# 12V_-_5V_Buck_1A_-_LM3485_v2.net
KiCad netlist of a schematic drawn in EAGLE
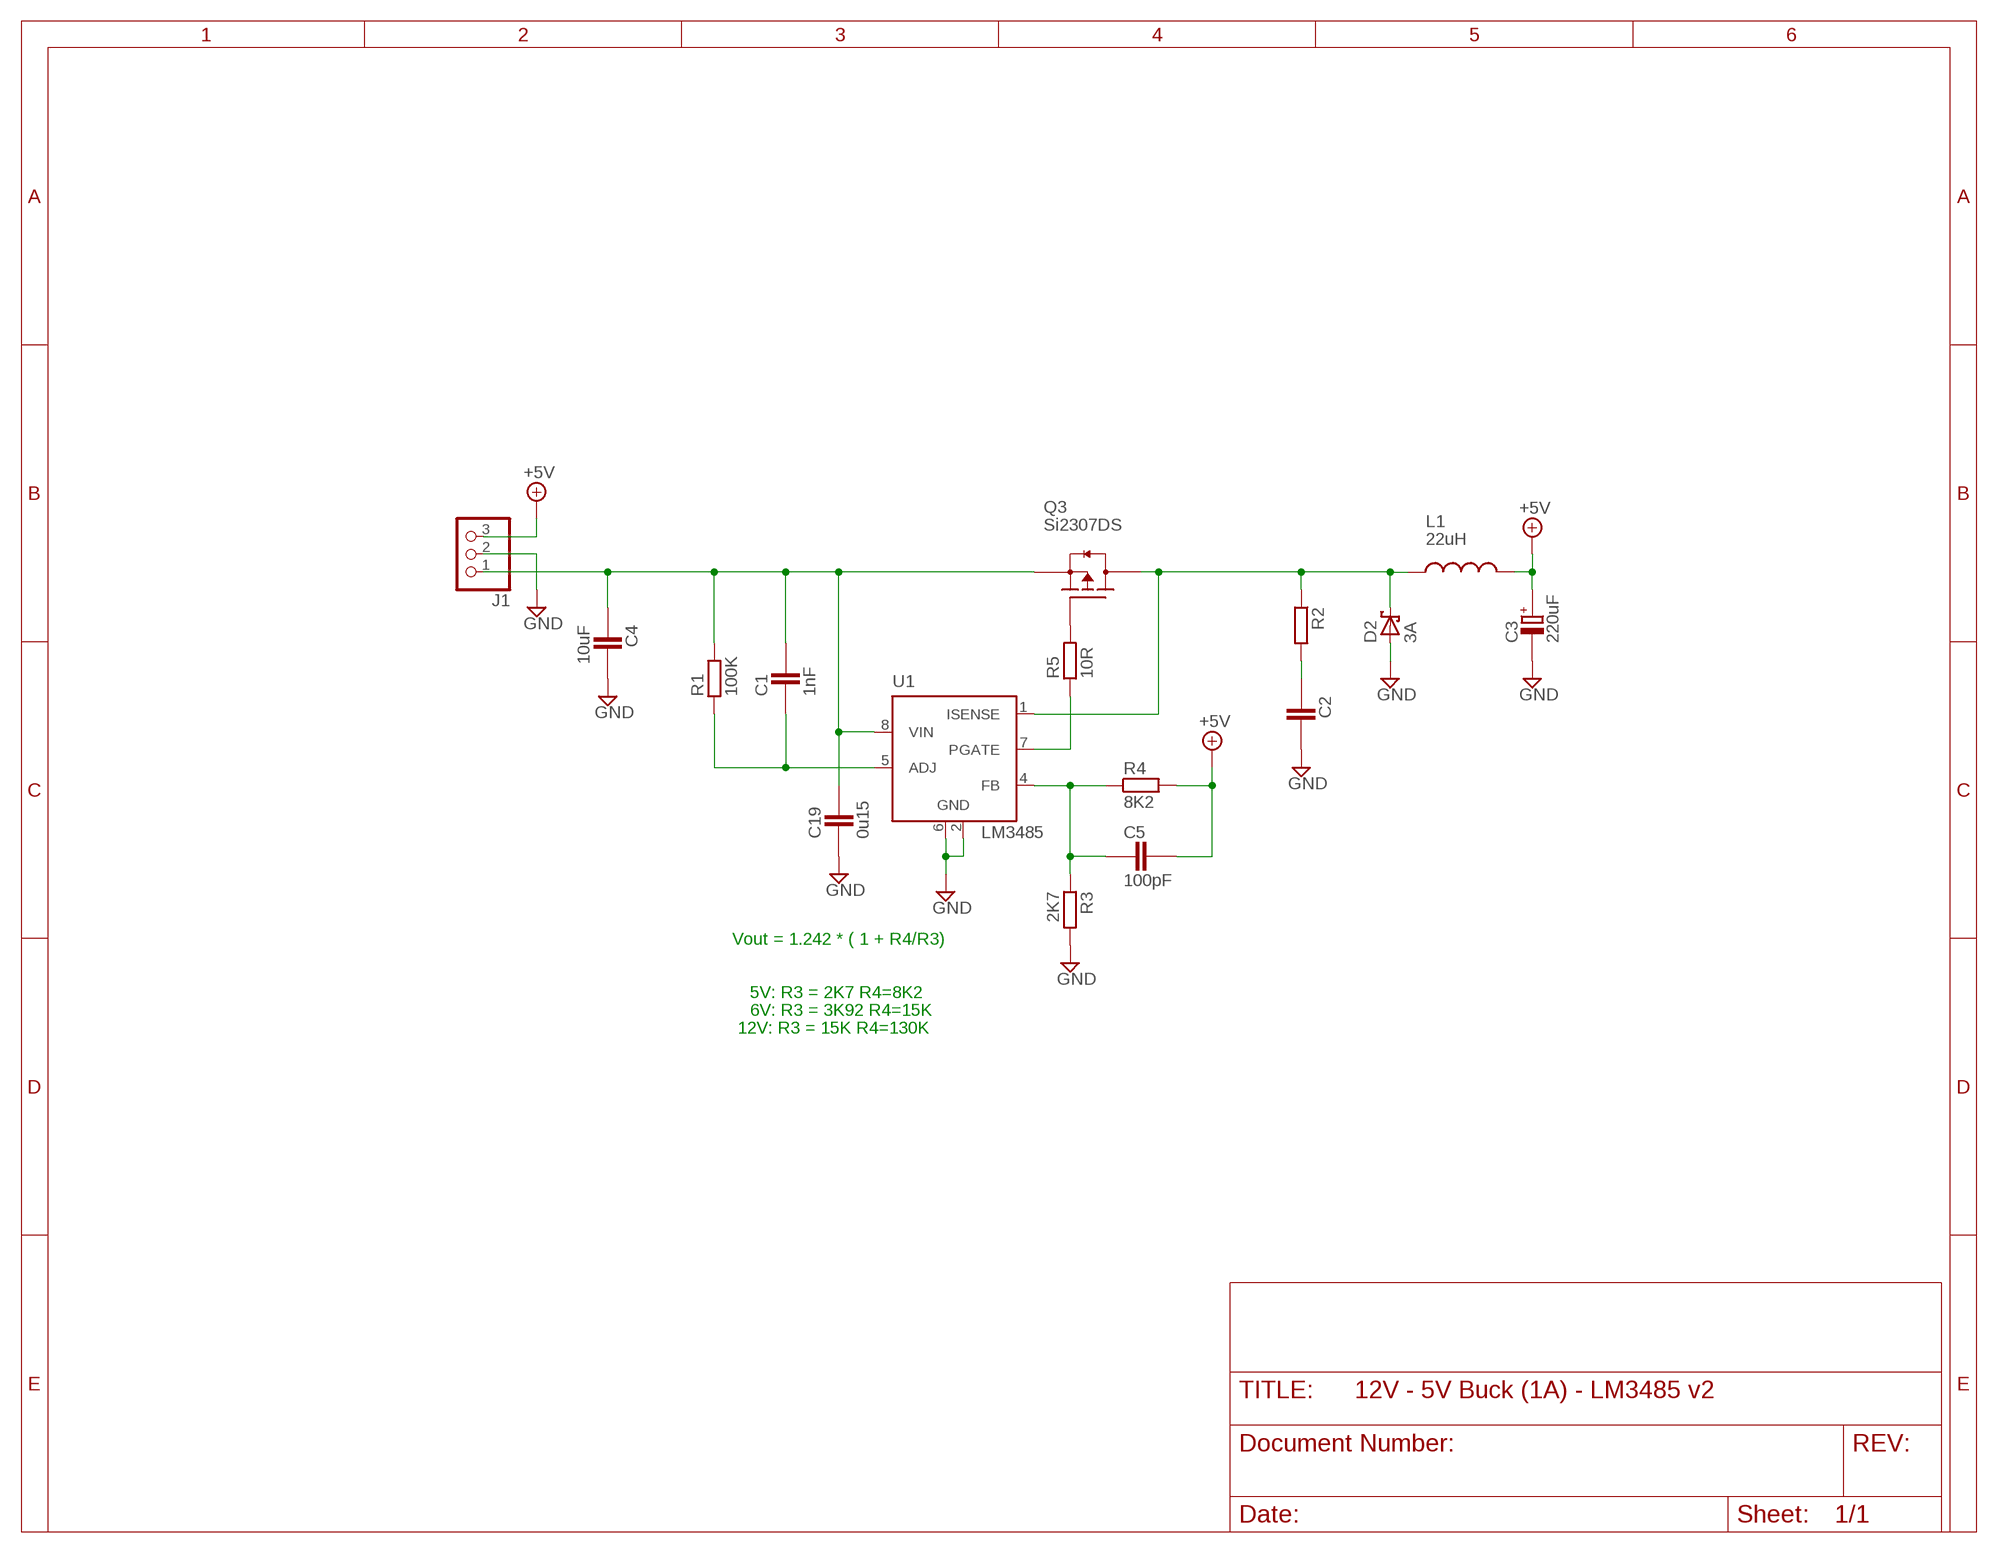
[diagram p0: schematic, sheet 1]

(export (version "E")
  (design (tool "Eeschema 10.0.6"))
  (components
    (comp (ref "C1")
      (value "1nF")
      (footprint "eagle-import:CAP2012X70N")
      (libsource (lib "eagle-import") (part "CAPACITOR_0805N"))
    )
    (comp (ref "C2")
      (value "CAPACITOR_0805N")
      (footprint "eagle-import:CAP2012X70N")
      (libsource (lib "eagle-import") (part "CAPACITOR_0805N"))
    )
    (comp (ref "C3")
      (value "220uF")
      (footprint "eagle-import:CAPMP7343X310N")
      (libsource (lib "eagle-import") (part "POLARISED_D_CASE"))
    )
    (comp (ref "C4")
      (value "10uF")
      (footprint "eagle-import:CAPC3225X168N")
      (libsource (lib "eagle-import") (part "CAPACITOR_1210"))
    )
    (comp (ref "C5")
      (value "100pF")
      (footprint "eagle-import:CAP2012X70N")
      (libsource (lib "eagle-import") (part "CAPACITOR_0805N"))
    )
    (comp (ref "C19")
      (value "0u15")
      (footprint "eagle-import:CAPC1608X92N")
      (libsource (lib "eagle-import") (part "CAPACITOR_0603"))
    )
    (comp (ref "D2")
      (value "3A")
      (footprint "eagle-import:DIOM7959X265N")
      (libsource (lib "eagle-import") (part "SCHOTTKY_SMC"))
    )
    (comp (ref "J1")
      (value "PINHD-1X3")
      (footprint "eagle-import:1X03")
      (libsource (lib "eagle-import") (part "PINHD-1X3"))
    )
    (comp (ref "L1")
      (value "22uH")
      (footprint "eagle-import:DO3316P")
      (libsource (lib "eagle-import") (part "DO3316P"))
    )
    (comp (ref "Q3")
      (value "Si2307DS")
      (footprint "eagle-import:SOT95P280X135-3N")
      (libsource (lib "eagle-import") (part "MOSFET-PCH_SOT-23"))
    )
    (comp (ref "R1")
      (value "100K")
      (footprint "eagle-import:RESC1608X55N")
      (libsource (lib "eagle-import") (part "RESISTOR_0603"))
    )
    (comp (ref "R2")
      (value "RESISTOR_0603")
      (footprint "eagle-import:RESC1608X55N")
      (libsource (lib "eagle-import") (part "RESISTOR_0603"))
    )
    (comp (ref "R3")
      (value "2K7")
      (footprint "eagle-import:RESC2012X70N")
      (libsource (lib "eagle-import") (part "RESISTOR_0805"))
    )
    (comp (ref "R4")
      (value "8K2")
      (footprint "eagle-import:RESC2012X70N")
      (libsource (lib "eagle-import") (part "RESISTOR_0805"))
    )
    (comp (ref "R5")
      (value "10R")
      (footprint "eagle-import:RESC1608X55N")
      (libsource (lib "eagle-import") (part "RESISTOR_0603"))
    )
    (comp (ref "U1")
      (value "LM3485")
      (footprint "eagle-import:MSOP08")
      (libsource (lib "eagle-import") (part "LM3485"))
    )
  )
  (nets
    (net (code "1") (name "+5V") (class "Default")
      (node (ref "C3") (pin "+") (pinfunction "+_+") (pintype "passive"))
      (node (ref "C5") (pin "2") (pinfunction "2_2") (pintype "passive"))
      (node (ref "J1") (pin "3") (pinfunction "3_3") (pintype "passive"))
      (node (ref "L1") (pin "2") (pinfunction "2_2") (pintype "passive"))
      (node (ref "R4") (pin "2") (pinfunction "2_2") (pintype "passive"))
    )
    (net (code "2") (name "GND") (class "Default")
      (node (ref "C19") (pin "1") (pinfunction "1_1") (pintype "passive"))
      (node (ref "C2") (pin "2") (pinfunction "2_2") (pintype "passive"))
      (node (ref "C3") (pin "-") (pinfunction "-_-") (pintype "passive"))
      (node (ref "C4") (pin "2") (pinfunction "2_2") (pintype "passive"))
      (node (ref "D2") (pin "A") (pinfunction "A_A") (pintype "passive"))
      (node (ref "J1") (pin "2") (pinfunction "2_2") (pintype "passive"))
      (node (ref "R3") (pin "2") (pinfunction "2_2") (pintype "passive"))
      (node (ref "U1") (pin "2") (pinfunction "GND_2") (pintype "power_in"))
      (node (ref "U1") (pin "6") (pinfunction "GND_6") (pintype "power_in"))
    )
    (net (code "3") (name "Net-(C2-Pad1)") (class "Default")
      (node (ref "C2") (pin "1") (pinfunction "1_1") (pintype "passive"))
      (node (ref "R2") (pin "2") (pinfunction "2_2") (pintype "passive"))
    )
    (net (code "4") (name "Net-(Q3-D)") (class "Default")
      (node (ref "D2") (pin "K") (pinfunction "K_K") (pintype "passive"))
      (node (ref "L1") (pin "1") (pinfunction "1_1") (pintype "passive"))
      (node (ref "Q3") (pin "3") (pinfunction "D_3") (pintype "passive"))
      (node (ref "R2") (pin "1") (pinfunction "1_1") (pintype "passive"))
      (node (ref "U1") (pin "1") (pinfunction "ISENSE_1") (pintype "input"))
    )
    (net (code "5") (name "Net-(Q3-G)") (class "Default")
      (node (ref "Q3") (pin "1") (pinfunction "G_1") (pintype "passive"))
      (node (ref "R5") (pin "2") (pinfunction "2_2") (pintype "passive"))
    )
    (net (code "6") (name "Net-(Q3-S)") (class "Default")
      (node (ref "C1") (pin "2") (pinfunction "2_2") (pintype "passive"))
      (node (ref "C19") (pin "2") (pinfunction "2_2") (pintype "passive"))
      (node (ref "C4") (pin "1") (pinfunction "1_1") (pintype "passive"))
      (node (ref "J1") (pin "1") (pinfunction "1_1") (pintype "passive"))
      (node (ref "Q3") (pin "2") (pinfunction "S_2") (pintype "passive"))
      (node (ref "R1") (pin "2") (pinfunction "2_2") (pintype "passive"))
      (node (ref "U1") (pin "8") (pinfunction "VIN_8") (pintype "input"))
    )
    (net (code "7") (name "Net-(U1-ADJ)") (class "Default")
      (node (ref "C1") (pin "1") (pinfunction "1_1") (pintype "passive"))
      (node (ref "R1") (pin "1") (pinfunction "1_1") (pintype "passive"))
      (node (ref "U1") (pin "5") (pinfunction "ADJ_5") (pintype "input"))
    )
    (net (code "8") (name "Net-(U1-FB)") (class "Default")
      (node (ref "C5") (pin "1") (pinfunction "1_1") (pintype "passive"))
      (node (ref "R3") (pin "1") (pinfunction "1_1") (pintype "passive"))
      (node (ref "R4") (pin "1") (pinfunction "1_1") (pintype "passive"))
      (node (ref "U1") (pin "4") (pinfunction "FB_4") (pintype "input"))
    )
    (net (code "9") (name "Net-(U1-PGATE)") (class "Default")
      (node (ref "R5") (pin "1") (pinfunction "1_1") (pintype "passive"))
      (node (ref "U1") (pin "7") (pinfunction "PGATE_7") (pintype "output"))
    )
  )
)
